# HDJD-S822_Color_Sensor_Breakout-v1_0.net
KiCad netlist of a schematic drawn in EAGLE
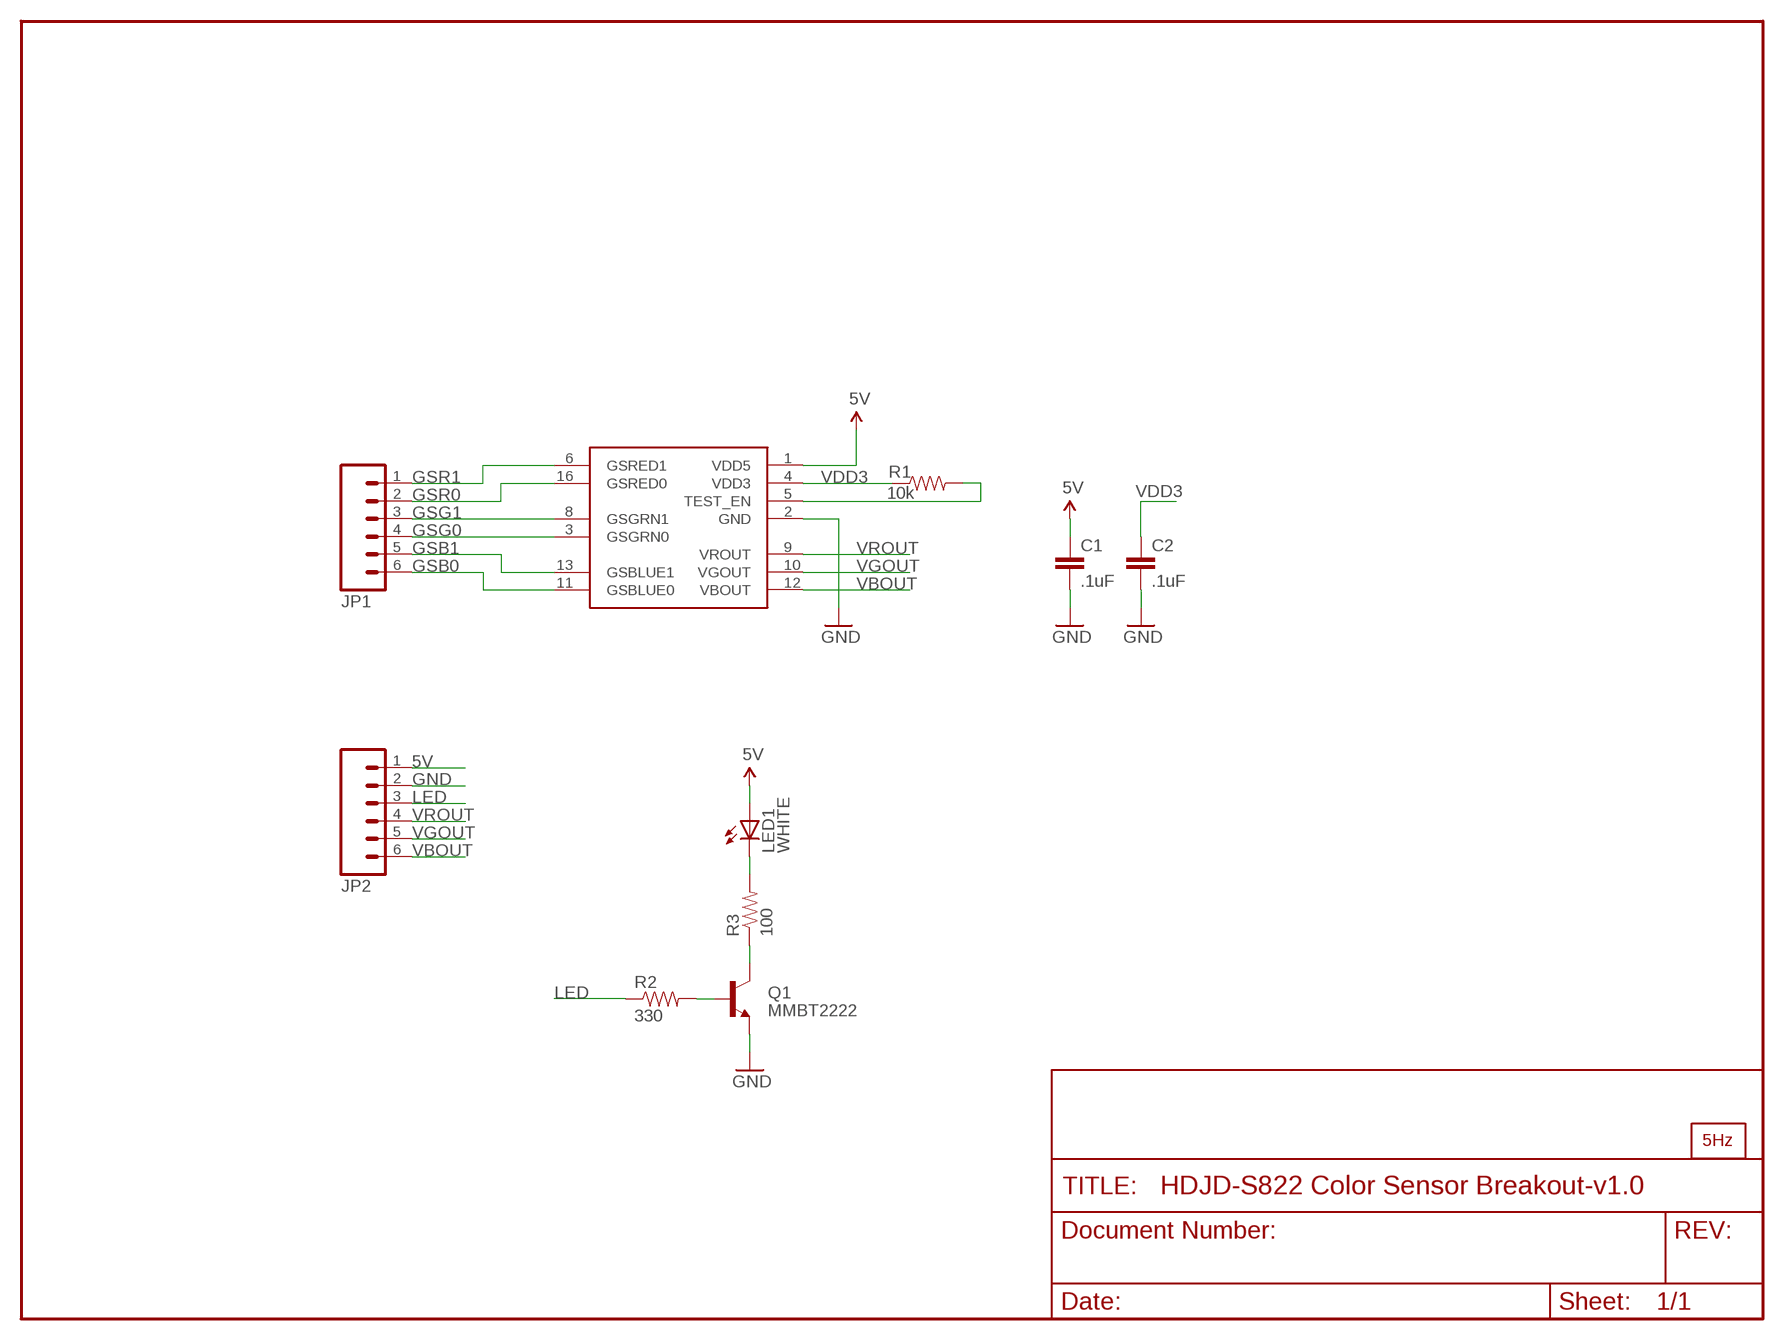
[diagram p0: schematic, sheet 1]

(export (version "E")
  (design (tool "Eeschema 10.0.6"))
  (components
    (comp (ref "C1")
      (value ".1uF")
      (footprint "eagle-import:0402-CAP")
      (libsource (lib "eagle-import") (part "CAP0402-CAP"))
    )
    (comp (ref "C2")
      (value ".1uF")
      (footprint "eagle-import:0402-CAP")
      (libsource (lib "eagle-import") (part "CAP0402-CAP"))
    )
    (comp (ref "JP1")
      (value "M06SIP")
      (footprint "eagle-import:1X06")
      (libsource (lib "eagle-import") (part "M06SIP"))
    )
    (comp (ref "JP2")
      (value "M06SIP")
      (footprint "eagle-import:1X06")
      (libsource (lib "eagle-import") (part "M06SIP"))
    )
    (comp (ref "LED1")
      (value "WHITE")
      (footprint "eagle-import:LED-0603")
      (libsource (lib "eagle-import") (part "LED0603"))
    )
    (comp (ref "Q1")
      (value "MMBT2222")
      (footprint "eagle-import:SOT23-3")
      (libsource (lib "eagle-import") (part "TRANSISTOR_NPNSOT23-3"))
    )
    (comp (ref "R1")
      (value "10k")
      (footprint "eagle-import:0402-RES")
      (libsource (lib "eagle-import") (part "RESISTOR0402-RES"))
    )
    (comp (ref "R2")
      (value "330")
      (footprint "eagle-import:0402-RES")
      (libsource (lib "eagle-import") (part "RESISTOR0402-RES"))
    )
    (comp (ref "R3")
      (value "100")
      (footprint "eagle-import:0402-RES")
      (libsource (lib "eagle-import") (part "RESISTOR0402-RES"))
    )
    (comp (ref "U$1")
      (value "HDJD-S822-QR999ROUNDEDTHERMALPAD")
      (footprint "eagle-import:QFN-16-(ROUNDED0THERMAL-PAD)")
      (libsource (lib "eagle-import") (part "HDJD-S822-QR999ROUNDEDTHERMALPAD"))
    )
    (comp (ref "U$2")
      (value "LOGO2_SILKL5MM")
      (footprint "eagle-import:LARGO2_5MM")
      (libsource (lib "eagle-import") (part "LOGO2_SILKL5MM"))
    )
  )
  (nets
    (net (code "1") (name "/GSB0") (class "Default")
      (node (ref "JP1") (pin "6") (pinfunction "6_6") (pintype "passive"))
      (node (ref "U$1") (pin "11") (pinfunction "GSBLUE0_11") (pintype "bidirectional"))
    )
    (net (code "2") (name "/GSB1") (class "Default")
      (node (ref "JP1") (pin "5") (pinfunction "5_5") (pintype "passive"))
      (node (ref "U$1") (pin "13") (pinfunction "GSBLUE1_13") (pintype "bidirectional"))
    )
    (net (code "3") (name "/GSG0") (class "Default")
      (node (ref "JP1") (pin "4") (pinfunction "4_4") (pintype "passive"))
      (node (ref "U$1") (pin "3") (pinfunction "GSGRN0_3") (pintype "bidirectional"))
    )
    (net (code "4") (name "/GSG1") (class "Default")
      (node (ref "JP1") (pin "3") (pinfunction "3_3") (pintype "passive"))
      (node (ref "U$1") (pin "8") (pinfunction "GSGRN1_8") (pintype "bidirectional"))
    )
    (net (code "5") (name "/GSR0") (class "Default")
      (node (ref "JP1") (pin "2") (pinfunction "2_2") (pintype "passive"))
      (node (ref "U$1") (pin "16") (pinfunction "GSRED0_16") (pintype "bidirectional"))
    )
    (net (code "6") (name "/GSR1") (class "Default")
      (node (ref "JP1") (pin "1") (pinfunction "1_1") (pintype "passive"))
      (node (ref "U$1") (pin "6") (pinfunction "GSRED1_6") (pintype "bidirectional"))
    )
    (net (code "7") (name "/LED") (class "Default")
      (node (ref "JP2") (pin "3") (pinfunction "3_3") (pintype "passive"))
      (node (ref "R2") (pin "1") (pinfunction "1_1") (pintype "passive"))
    )
    (net (code "8") (name "/VBOUT") (class "Default")
      (node (ref "JP2") (pin "6") (pinfunction "6_6") (pintype "passive"))
      (node (ref "U$1") (pin "12") (pinfunction "VBOUT_12") (pintype "bidirectional"))
    )
    (net (code "9") (name "/VDD3") (class "Default")
      (node (ref "C2") (pin "1") (pinfunction "1_1") (pintype "passive"))
      (node (ref "R1") (pin "1") (pinfunction "1_1") (pintype "passive"))
      (node (ref "U$1") (pin "4") (pinfunction "VDD3_4") (pintype "bidirectional"))
    )
    (net (code "10") (name "/VGOUT") (class "Default")
      (node (ref "JP2") (pin "5") (pinfunction "5_5") (pintype "passive"))
      (node (ref "U$1") (pin "10") (pinfunction "VGOUT_10") (pintype "bidirectional"))
    )
    (net (code "11") (name "/VROUT") (class "Default")
      (node (ref "JP2") (pin "4") (pinfunction "4_4") (pintype "passive"))
      (node (ref "U$1") (pin "9") (pinfunction "VROUT_9") (pintype "bidirectional"))
    )
    (net (code "12") (name "5V") (class "Default")
      (node (ref "C1") (pin "1") (pinfunction "1_1") (pintype "passive"))
      (node (ref "JP2") (pin "1") (pinfunction "1_1") (pintype "passive"))
      (node (ref "LED1") (pin "A") (pinfunction "A_A") (pintype "passive"))
      (node (ref "U$1") (pin "1") (pinfunction "VDD5_1") (pintype "bidirectional"))
    )
    (net (code "13") (name "GND") (class "Default")
      (node (ref "C1") (pin "2") (pinfunction "2_2") (pintype "passive"))
      (node (ref "C2") (pin "2") (pinfunction "2_2") (pintype "passive"))
      (node (ref "JP2") (pin "2") (pinfunction "2_2") (pintype "passive"))
      (node (ref "Q1") (pin "2") (pinfunction "E_2") (pintype "passive"))
      (node (ref "U$1") (pin "2") (pinfunction "GND_2") (pintype "bidirectional"))
    )
    (net (code "14") (name "Net-(LED1-PadC)") (class "Default")
      (node (ref "LED1") (pin "C") (pinfunction "C_C") (pintype "passive"))
      (node (ref "R3") (pin "2") (pinfunction "2_2") (pintype "passive"))
    )
    (net (code "15") (name "Net-(Q1-B)") (class "Default")
      (node (ref "Q1") (pin "1") (pinfunction "B_1") (pintype "passive"))
      (node (ref "R2") (pin "2") (pinfunction "2_2") (pintype "passive"))
    )
    (net (code "16") (name "Net-(Q1-C)") (class "Default")
      (node (ref "Q1") (pin "3") (pinfunction "C_3") (pintype "passive"))
      (node (ref "R3") (pin "1") (pinfunction "1_1") (pintype "passive"))
    )
    (net (code "17") (name "Net-(U$1-TEST_EN)") (class "Default")
      (node (ref "R1") (pin "2") (pinfunction "2_2") (pintype "passive"))
      (node (ref "U$1") (pin "5") (pinfunction "TEST_EN_5") (pintype "bidirectional"))
    )
  )
)
